# Relay_PCB.net
KiCad netlist of a schematic drawn in Altium Designer
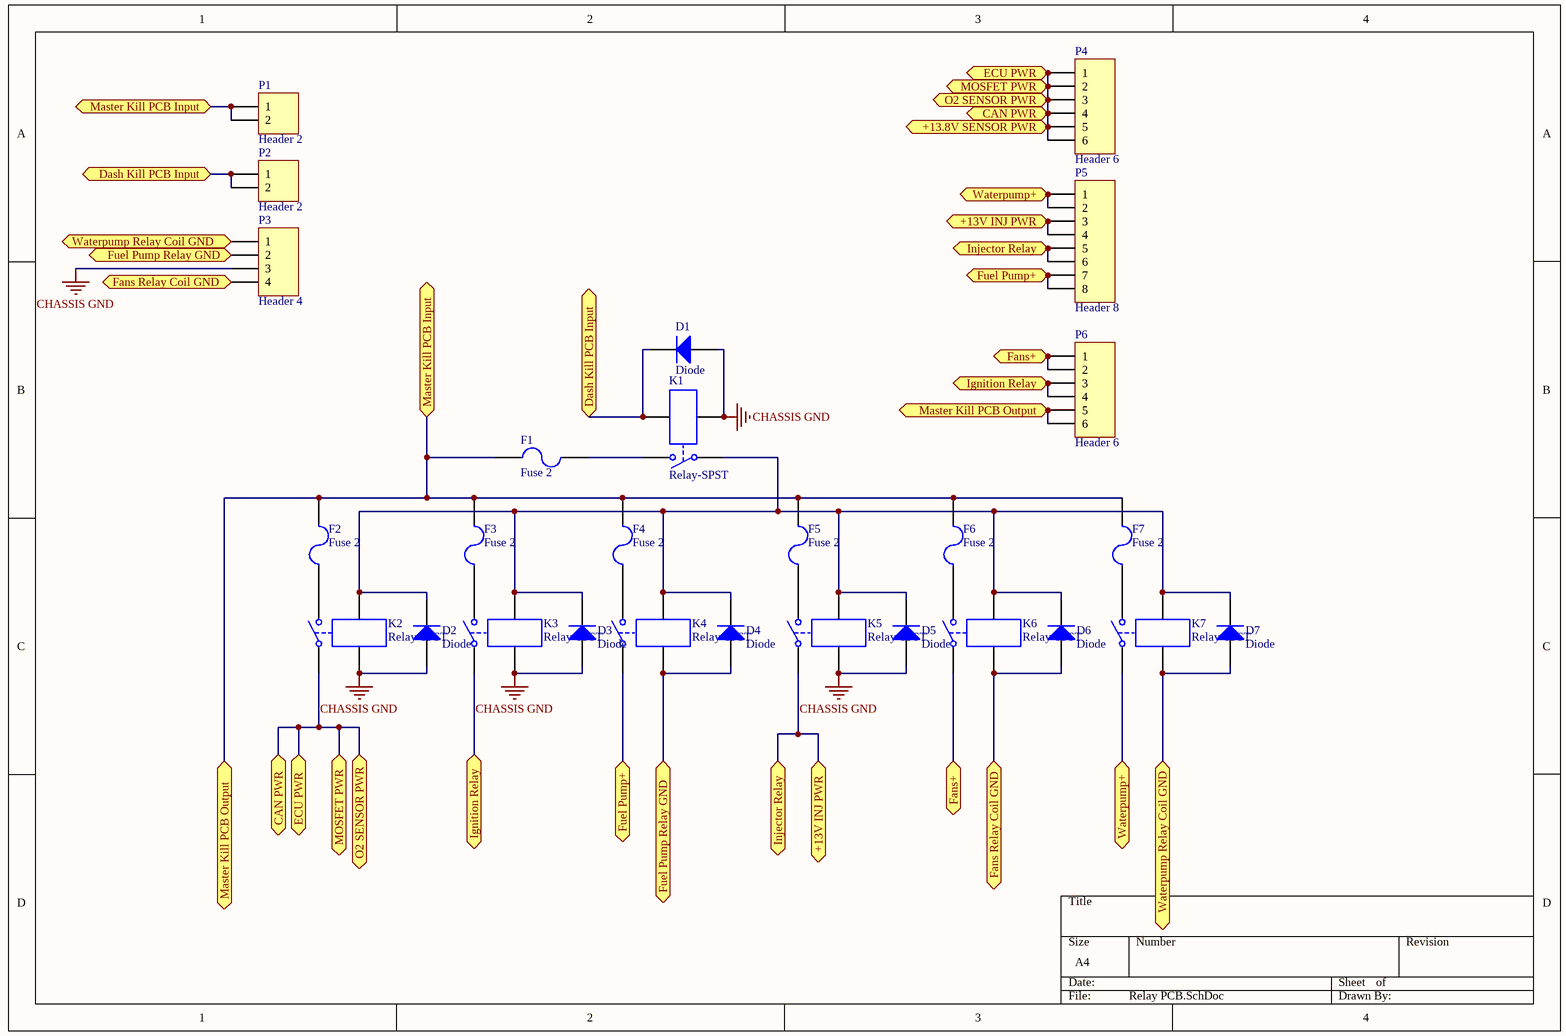
[diagram p0: Relay PCB.SchDoc]

(export (version "E")
  (design (tool "Eeschema 10.0.6"))
  (components
    (comp (ref "D1")
      (value "Diode")
      (footprint "SMC")
      (description "Default Diode")
      (fields (field (name "PUBLISHER") "Altium Limited"))
      (libsource (lib "Miscellaneous Devices") (part "Diode"))
    )
    (comp (ref "D2")
      (value "Diode")
      (footprint "SMC")
      (description "Default Diode")
      (fields (field (name "PUBLISHER") "Altium Limited"))
      (libsource (lib "Miscellaneous Devices") (part "Diode"))
    )
    (comp (ref "D3")
      (value "Diode")
      (footprint "SMC")
      (description "Default Diode")
      (fields (field (name "PUBLISHER") "Altium Limited"))
      (libsource (lib "Miscellaneous Devices") (part "Diode"))
    )
    (comp (ref "D4")
      (value "Diode")
      (footprint "SMC")
      (description "Default Diode")
      (fields (field (name "PUBLISHER") "Altium Limited"))
      (libsource (lib "Miscellaneous Devices") (part "Diode"))
    )
    (comp (ref "D5")
      (value "Diode")
      (footprint "SMC")
      (description "Default Diode")
      (fields (field (name "PUBLISHER") "Altium Limited"))
      (libsource (lib "Miscellaneous Devices") (part "Diode"))
    )
    (comp (ref "D6")
      (value "Diode")
      (footprint "SMC")
      (description "Default Diode")
      (fields (field (name "PUBLISHER") "Altium Limited"))
      (libsource (lib "Miscellaneous Devices") (part "Diode"))
    )
    (comp (ref "D7")
      (value "Diode")
      (footprint "SMC")
      (description "Default Diode")
      (fields (field (name "PUBLISHER") "Altium Limited"))
      (libsource (lib "Miscellaneous Devices") (part "Diode"))
    )
    (comp (ref "F1")
      (value "Fuse 2")
      (footprint "PIN-W2/E2.8")
      (description "Fuse")
      (fields (field (name "PUBLISHER") "Altium Limited"))
      (libsource (lib "Miscellaneous Devices") (part "Fuse 2"))
    )
    (comp (ref "F2")
      (value "Fuse 2")
      (footprint "PIN-W2/E2.8")
      (description "Fuse")
      (fields (field (name "PUBLISHER") "Altium Limited"))
      (libsource (lib "Miscellaneous Devices") (part "Fuse 2"))
    )
    (comp (ref "F3")
      (value "Fuse 2")
      (footprint "PIN-W2/E2.8")
      (description "Fuse")
      (fields (field (name "PUBLISHER") "Altium Limited"))
      (libsource (lib "Miscellaneous Devices") (part "Fuse 2"))
    )
    (comp (ref "F4")
      (value "Fuse 2")
      (footprint "PIN-W2/E2.8")
      (description "Fuse")
      (fields (field (name "PUBLISHER") "Altium Limited"))
      (libsource (lib "Miscellaneous Devices") (part "Fuse 2"))
    )
    (comp (ref "F5")
      (value "Fuse 2")
      (footprint "PIN-W2/E2.8")
      (description "Fuse")
      (fields (field (name "PUBLISHER") "Altium Limited"))
      (libsource (lib "Miscellaneous Devices") (part "Fuse 2"))
    )
    (comp (ref "F6")
      (value "Fuse 2")
      (footprint "PIN-W2/E2.8")
      (description "Fuse")
      (fields (field (name "PUBLISHER") "Altium Limited"))
      (libsource (lib "Miscellaneous Devices") (part "Fuse 2"))
    )
    (comp (ref "F7")
      (value "Fuse 2")
      (footprint "PIN-W2/E2.8")
      (description "Fuse")
      (fields (field (name "PUBLISHER") "Altium Limited"))
      (libsource (lib "Miscellaneous Devices") (part "Fuse 2"))
    )
    (comp (ref "K1")
      (value "Relay-SPST")
      (footprint "MODULE4")
      (description "Single-Pole Single-Throw Relay")
      (fields (field (name "PUBLISHER") "Altium Limited"))
      (libsource (lib "Miscellaneous Devices") (part "Relay-SPST"))
    )
    (comp (ref "K2")
      (value "Relay-SPST")
      (footprint "MODULE4")
      (description "Single-Pole Single-Throw Relay")
      (fields (field (name "PUBLISHER") "Altium Limited"))
      (libsource (lib "Miscellaneous Devices") (part "Relay-SPST"))
    )
    (comp (ref "K3")
      (value "Relay-SPST")
      (footprint "MODULE4")
      (description "Single-Pole Single-Throw Relay")
      (fields (field (name "PUBLISHER") "Altium Limited"))
      (libsource (lib "Miscellaneous Devices") (part "Relay-SPST"))
    )
    (comp (ref "K4")
      (value "Relay-SPST")
      (footprint "MODULE4")
      (description "Single-Pole Single-Throw Relay")
      (fields (field (name "PUBLISHER") "Altium Limited"))
      (libsource (lib "Miscellaneous Devices") (part "Relay-SPST"))
    )
    (comp (ref "K5")
      (value "Relay-SPST")
      (footprint "MODULE4")
      (description "Single-Pole Single-Throw Relay")
      (fields (field (name "PUBLISHER") "Altium Limited"))
      (libsource (lib "Miscellaneous Devices") (part "Relay-SPST"))
    )
    (comp (ref "K6")
      (value "Relay-SPST")
      (footprint "MODULE4")
      (description "Single-Pole Single-Throw Relay")
      (fields (field (name "PUBLISHER") "Altium Limited"))
      (libsource (lib "Miscellaneous Devices") (part "Relay-SPST"))
    )
    (comp (ref "K7")
      (value "Relay-SPST")
      (footprint "MODULE4")
      (description "Single-Pole Single-Throw Relay")
      (fields (field (name "PUBLISHER") "Altium Limited"))
      (libsource (lib "Miscellaneous Devices") (part "Relay-SPST"))
    )
    (comp (ref "P1")
      (value "Header 2")
      (footprint "HDR1X2")
      (description "Header, 2-Pin")
      (fields (field (name "PUBLISHER") "Altium Limited"))
      (libsource (lib "Miscellaneous Connectors") (part "Header 2"))
    )
    (comp (ref "P2")
      (value "Header 2")
      (footprint "HDR1X2")
      (description "Header, 2-Pin")
      (fields (field (name "PUBLISHER") "Altium Limited"))
      (libsource (lib "Miscellaneous Connectors") (part "Header 2"))
    )
    (comp (ref "P3")
      (value "Header 4")
      (footprint "HDR1X4")
      (description "Header, 4-Pin")
      (fields (field (name "PUBLISHER") "Altium Limited"))
      (libsource (lib "Miscellaneous Connectors") (part "Header 4"))
    )
    (comp (ref "P4")
      (value "Header 6")
      (footprint "HDR1X6")
      (description "Header, 6-Pin")
      (fields (field (name "PUBLISHER") "Altium Limited"))
      (libsource (lib "Miscellaneous Connectors") (part "Header 6"))
    )
    (comp (ref "P5")
      (value "Header 8")
      (footprint "HDR1X8")
      (description "Header, 8-Pin")
      (fields (field (name "PUBLISHER") "Altium Limited"))
      (libsource (lib "Miscellaneous Connectors") (part "Header 8"))
    )
    (comp (ref "P6")
      (value "Header 6")
      (footprint "HDR1X6")
      (description "Header, 6-Pin")
      (fields (field (name "PUBLISHER") "Altium Limited"))
      (libsource (lib "Miscellaneous Connectors") (part "Header 6"))
    )
  )
  (nets
    (net (code "1") (name "/+13.8V SENSOR PWR") (class "Default")
      (node (ref "K2") (pin "1") (pinfunction "1_1") (pintype "passive"))
      (node (ref "P4") (pin "1") (pinfunction "1_1") (pintype "passive"))
      (node (ref "P4") (pin "2") (pinfunction "2_2") (pintype "passive"))
      (node (ref "P4") (pin "3") (pinfunction "3_3") (pintype "passive"))
      (node (ref "P4") (pin "4") (pinfunction "4_4") (pintype "passive"))
      (node (ref "P4") (pin "5") (pinfunction "5_5") (pintype "passive"))
      (node (ref "P4") (pin "6") (pinfunction "6_6") (pintype "passive"))
    )
    (net (code "2") (name "/+13V INJ PWR") (class "Default")
      (node (ref "K5") (pin "1") (pinfunction "1_1") (pintype "passive"))
      (node (ref "P5") (pin "3") (pinfunction "3_3") (pintype "passive"))
      (node (ref "P5") (pin "4") (pinfunction "4_4") (pintype "passive"))
      (node (ref "P5") (pin "5") (pinfunction "5_5") (pintype "passive"))
      (node (ref "P5") (pin "6") (pinfunction "6_6") (pintype "passive"))
    )
    (net (code "3") (name "/Dash Kill PCB Input") (class "Default")
      (node (ref "D1") (pin "2") (pinfunction "K_2") (pintype "passive"))
      (node (ref "K1") (pin "4") (pinfunction "4_4") (pintype "passive"))
      (node (ref "P2") (pin "1") (pinfunction "1_1") (pintype "passive"))
      (node (ref "P2") (pin "2") (pinfunction "2_2") (pintype "passive"))
    )
    (net (code "4") (name "/Fans Relay Coil GND") (class "Default")
      (node (ref "D6") (pin "1") (pinfunction "A_1") (pintype "passive"))
      (node (ref "K6") (pin "3") (pinfunction "3_3") (pintype "passive"))
      (node (ref "P3") (pin "4") (pinfunction "4_4") (pintype "passive"))
    )
    (net (code "5") (name "/Fans+") (class "Default")
      (node (ref "K6") (pin "1") (pinfunction "1_1") (pintype "passive"))
      (node (ref "P6") (pin "1") (pinfunction "1_1") (pintype "passive"))
      (node (ref "P6") (pin "2") (pinfunction "2_2") (pintype "passive"))
    )
    (net (code "6") (name "/Fuel Pump Relay GND") (class "Default")
      (node (ref "D4") (pin "1") (pinfunction "A_1") (pintype "passive"))
      (node (ref "K4") (pin "3") (pinfunction "3_3") (pintype "passive"))
      (node (ref "P3") (pin "2") (pinfunction "2_2") (pintype "passive"))
    )
    (net (code "7") (name "/Fuel Pump+") (class "Default")
      (node (ref "K4") (pin "1") (pinfunction "1_1") (pintype "passive"))
      (node (ref "P5") (pin "7") (pinfunction "7_7") (pintype "passive"))
      (node (ref "P5") (pin "8") (pinfunction "8_8") (pintype "passive"))
    )
    (net (code "8") (name "/Ignition Relay") (class "Default")
      (node (ref "K3") (pin "1") (pinfunction "1_1") (pintype "passive"))
      (node (ref "P6") (pin "3") (pinfunction "3_3") (pintype "passive"))
      (node (ref "P6") (pin "4") (pinfunction "4_4") (pintype "passive"))
    )
    (net (code "9") (name "/Master Kill PCB Input") (class "Default")
      (node (ref "F1") (pin "1") (pinfunction "1_1") (pintype "passive"))
      (node (ref "F2") (pin "2") (pinfunction "2_2") (pintype "passive"))
      (node (ref "F3") (pin "2") (pinfunction "2_2") (pintype "passive"))
      (node (ref "F4") (pin "2") (pinfunction "2_2") (pintype "passive"))
      (node (ref "F5") (pin "2") (pinfunction "2_2") (pintype "passive"))
      (node (ref "F6") (pin "2") (pinfunction "2_2") (pintype "passive"))
      (node (ref "F7") (pin "2") (pinfunction "2_2") (pintype "passive"))
      (node (ref "P1") (pin "1") (pinfunction "1_1") (pintype "passive"))
      (node (ref "P1") (pin "2") (pinfunction "2_2") (pintype "passive"))
      (node (ref "P6") (pin "5") (pinfunction "5_5") (pintype "passive"))
      (node (ref "P6") (pin "6") (pinfunction "6_6") (pintype "passive"))
    )
    (net (code "10") (name "/Waterpump Relay Coil GND") (class "Default")
      (node (ref "D7") (pin "1") (pinfunction "A_1") (pintype "passive"))
      (node (ref "K7") (pin "3") (pinfunction "3_3") (pintype "passive"))
      (node (ref "P3") (pin "1") (pinfunction "1_1") (pintype "passive"))
    )
    (net (code "11") (name "/Waterpump+") (class "Default")
      (node (ref "K7") (pin "1") (pinfunction "1_1") (pintype "passive"))
      (node (ref "P5") (pin "1") (pinfunction "1_1") (pintype "passive"))
      (node (ref "P5") (pin "2") (pinfunction "2_2") (pintype "passive"))
    )
    (net (code "12") (name "CHASSIS GND") (class "Default")
      (node (ref "D1") (pin "1") (pinfunction "A_1") (pintype "passive"))
      (node (ref "D2") (pin "1") (pinfunction "A_1") (pintype "passive"))
      (node (ref "D3") (pin "1") (pinfunction "A_1") (pintype "passive"))
      (node (ref "D5") (pin "1") (pinfunction "A_1") (pintype "passive"))
      (node (ref "K1") (pin "3") (pinfunction "3_3") (pintype "passive"))
      (node (ref "K2") (pin "3") (pinfunction "3_3") (pintype "passive"))
      (node (ref "K3") (pin "3") (pinfunction "3_3") (pintype "passive"))
      (node (ref "K5") (pin "3") (pinfunction "3_3") (pintype "passive"))
      (node (ref "P3") (pin "3") (pinfunction "3_3") (pintype "passive"))
    )
    (net (code "13") (name "Net-(D2-K)") (class "Default")
      (node (ref "D2") (pin "2") (pinfunction "K_2") (pintype "passive"))
      (node (ref "D3") (pin "2") (pinfunction "K_2") (pintype "passive"))
      (node (ref "D4") (pin "2") (pinfunction "K_2") (pintype "passive"))
      (node (ref "D5") (pin "2") (pinfunction "K_2") (pintype "passive"))
      (node (ref "D6") (pin "2") (pinfunction "K_2") (pintype "passive"))
      (node (ref "D7") (pin "2") (pinfunction "K_2") (pintype "passive"))
      (node (ref "K1") (pin "1") (pinfunction "1_1") (pintype "passive"))
      (node (ref "K2") (pin "4") (pinfunction "4_4") (pintype "passive"))
      (node (ref "K3") (pin "4") (pinfunction "4_4") (pintype "passive"))
      (node (ref "K4") (pin "4") (pinfunction "4_4") (pintype "passive"))
      (node (ref "K5") (pin "4") (pinfunction "4_4") (pintype "passive"))
      (node (ref "K6") (pin "4") (pinfunction "4_4") (pintype "passive"))
      (node (ref "K7") (pin "4") (pinfunction "4_4") (pintype "passive"))
    )
    (net (code "14") (name "Net-(F1-Pad2)") (class "Default")
      (node (ref "F1") (pin "2") (pinfunction "2_2") (pintype "passive"))
      (node (ref "K1") (pin "2") (pinfunction "2_2") (pintype "passive"))
    )
    (net (code "15") (name "Net-(F2-Pad1)") (class "Default")
      (node (ref "F2") (pin "1") (pinfunction "1_1") (pintype "passive"))
      (node (ref "K2") (pin "2") (pinfunction "2_2") (pintype "passive"))
    )
    (net (code "16") (name "Net-(F3-Pad1)") (class "Default")
      (node (ref "F3") (pin "1") (pinfunction "1_1") (pintype "passive"))
      (node (ref "K3") (pin "2") (pinfunction "2_2") (pintype "passive"))
    )
    (net (code "17") (name "Net-(F4-Pad1)") (class "Default")
      (node (ref "F4") (pin "1") (pinfunction "1_1") (pintype "passive"))
      (node (ref "K4") (pin "2") (pinfunction "2_2") (pintype "passive"))
    )
    (net (code "18") (name "Net-(F5-Pad1)") (class "Default")
      (node (ref "F5") (pin "1") (pinfunction "1_1") (pintype "passive"))
      (node (ref "K5") (pin "2") (pinfunction "2_2") (pintype "passive"))
    )
    (net (code "19") (name "Net-(F6-Pad1)") (class "Default")
      (node (ref "F6") (pin "1") (pinfunction "1_1") (pintype "passive"))
      (node (ref "K6") (pin "2") (pinfunction "2_2") (pintype "passive"))
    )
    (net (code "20") (name "Net-(F7-Pad1)") (class "Default")
      (node (ref "F7") (pin "1") (pinfunction "1_1") (pintype "passive"))
      (node (ref "K7") (pin "2") (pinfunction "2_2") (pintype "passive"))
    )
  )
)
